# LimitSwitchandMotorBoard.net
KiCad netlist of a schematic drawn in EAGLE
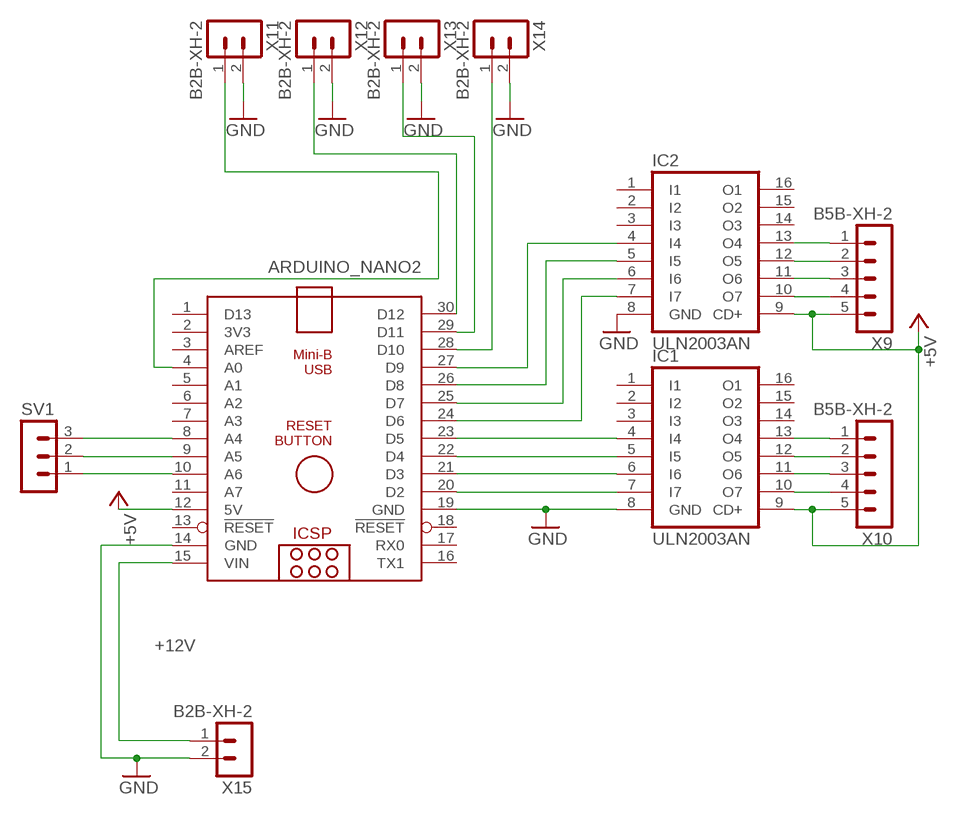
[diagram p0: schematic, sheet 1]

(export (version "E")
  (design (tool "Eeschema 10.0.6"))
  (components
    (comp (ref "ARDUINO_NANO2")
      (value "ARDUINO_NANO")
      (footprint "eagle-import:ARDUINO_NANO")
      (libsource (lib "eagle-import") (part "ARDUINO_NANO"))
    )
    (comp (ref "IC1")
      (value "ULN2003AN")
      (footprint "eagle-import:DIL16")
      (libsource (lib "eagle-import") (part "ULN2003AN"))
    )
    (comp (ref "IC2")
      (value "ULN2003AN")
      (footprint "eagle-import:DIL16")
      (libsource (lib "eagle-import") (part "ULN2003AN"))
    )
    (comp (ref "SV1")
      (value "MA03-1")
      (footprint "eagle-import:MA03-1")
      (libsource (lib "eagle-import") (part "MA03-1"))
    )
    (comp (ref "X9")
      (value "B5B-XH-2")
      (footprint "eagle-import:B5B-XH-A")
      (libsource (lib "eagle-import") (part "B5B-XH-2"))
    )
    (comp (ref "X10")
      (value "B5B-XH-2")
      (footprint "eagle-import:B5B-XH-A")
      (libsource (lib "eagle-import") (part "B5B-XH-2"))
    )
    (comp (ref "X11")
      (value "B2B-XH-2")
      (footprint "eagle-import:B2B-XH-A")
      (libsource (lib "eagle-import") (part "B2B-XH-2"))
    )
    (comp (ref "X12")
      (value "B2B-XH-2")
      (footprint "eagle-import:B2B-XH-A")
      (libsource (lib "eagle-import") (part "B2B-XH-2"))
    )
    (comp (ref "X13")
      (value "B2B-XH-2")
      (footprint "eagle-import:B2B-XH-A")
      (libsource (lib "eagle-import") (part "B2B-XH-2"))
    )
    (comp (ref "X14")
      (value "B2B-XH-2")
      (footprint "eagle-import:B2B-XH-A")
      (libsource (lib "eagle-import") (part "B2B-XH-2"))
    )
    (comp (ref "X15")
      (value "B2B-XH-2")
      (footprint "eagle-import:B2B-XH-A")
      (libsource (lib "eagle-import") (part "B2B-XH-2"))
    )
  )
  (nets
    (net (code "1") (name "+5V") (class "Default")
      (node (ref "ARDUINO_NANO2") (pin "12") (pinfunction "5V_12") (pintype "power_in"))
      (node (ref "IC1") (pin "9") (pinfunction "CD+_9") (pintype "passive"))
      (node (ref "IC2") (pin "9") (pinfunction "CD+_9") (pintype "passive"))
      (node (ref "X10") (pin "5") (pinfunction "5_5") (pintype "passive"))
      (node (ref "X9") (pin "5") (pinfunction "5_5") (pintype "passive"))
    )
    (net (code "2") (name "/+12V") (class "Default")
      (node (ref "ARDUINO_NANO2") (pin "15") (pinfunction "VIN_15") (pintype "power_in"))
      (node (ref "X15") (pin "1") (pinfunction "1_1") (pintype "passive"))
    )
    (net (code "3") (name "GND") (class "Default")
      (node (ref "ARDUINO_NANO2") (pin "14") (pinfunction "GND_14") (pintype "power_in"))
      (node (ref "ARDUINO_NANO2") (pin "19") (pinfunction "GND_19") (pintype "power_in"))
      (node (ref "IC1") (pin "8") (pinfunction "GND_8") (pintype "power_in"))
      (node (ref "IC2") (pin "8") (pinfunction "GND_8") (pintype "power_in"))
      (node (ref "X11") (pin "2") (pinfunction "2_2") (pintype "passive"))
      (node (ref "X12") (pin "2") (pinfunction "2_2") (pintype "passive"))
      (node (ref "X13") (pin "2") (pinfunction "2_2") (pintype "passive"))
      (node (ref "X14") (pin "2") (pinfunction "2_2") (pintype "passive"))
      (node (ref "X15") (pin "2") (pinfunction "2_2") (pintype "passive"))
    )
    (net (code "4") (name "Net-(ARDUINO_NANO2-A0)") (class "Default")
      (node (ref "ARDUINO_NANO2") (pin "4") (pinfunction "A0_4") (pintype "bidirectional"))
      (node (ref "X11") (pin "1") (pinfunction "1_1") (pintype "passive"))
    )
    (net (code "5") (name "Net-(ARDUINO_NANO2-A4)") (class "Default")
      (node (ref "ARDUINO_NANO2") (pin "8") (pinfunction "A4_8") (pintype "bidirectional"))
      (node (ref "SV1") (pin "3") (pinfunction "3_3") (pintype "passive"))
    )
    (net (code "6") (name "Net-(ARDUINO_NANO2-A5)") (class "Default")
      (node (ref "ARDUINO_NANO2") (pin "9") (pinfunction "A5_9") (pintype "bidirectional"))
      (node (ref "SV1") (pin "2") (pinfunction "2_2") (pintype "passive"))
    )
    (net (code "7") (name "Net-(ARDUINO_NANO2-A6)") (class "Default")
      (node (ref "ARDUINO_NANO2") (pin "10") (pinfunction "A6_10") (pintype "bidirectional"))
      (node (ref "SV1") (pin "1") (pinfunction "1_1") (pintype "passive"))
    )
    (net (code "8") (name "Net-(ARDUINO_NANO2-D2)") (class "Default")
      (node (ref "ARDUINO_NANO2") (pin "20") (pinfunction "D2_20") (pintype "bidirectional"))
      (node (ref "IC1") (pin "7") (pinfunction "I7_7") (pintype "input"))
    )
    (net (code "9") (name "Net-(ARDUINO_NANO2-D3)") (class "Default")
      (node (ref "ARDUINO_NANO2") (pin "21") (pinfunction "D3_21") (pintype "bidirectional"))
      (node (ref "IC1") (pin "6") (pinfunction "I6_6") (pintype "input"))
    )
    (net (code "10") (name "Net-(ARDUINO_NANO2-D4)") (class "Default")
      (node (ref "ARDUINO_NANO2") (pin "22") (pinfunction "D4_22") (pintype "bidirectional"))
      (node (ref "IC1") (pin "5") (pinfunction "I5_5") (pintype "input"))
    )
    (net (code "11") (name "Net-(ARDUINO_NANO2-D5)") (class "Default")
      (node (ref "ARDUINO_NANO2") (pin "23") (pinfunction "D5_23") (pintype "bidirectional"))
      (node (ref "IC1") (pin "4") (pinfunction "I4_4") (pintype "input"))
    )
    (net (code "12") (name "Net-(ARDUINO_NANO2-D6)") (class "Default")
      (node (ref "ARDUINO_NANO2") (pin "24") (pinfunction "D6_24") (pintype "bidirectional"))
      (node (ref "IC2") (pin "7") (pinfunction "I7_7") (pintype "input"))
    )
    (net (code "13") (name "Net-(ARDUINO_NANO2-D7)") (class "Default")
      (node (ref "ARDUINO_NANO2") (pin "25") (pinfunction "D7_25") (pintype "bidirectional"))
      (node (ref "IC2") (pin "6") (pinfunction "I6_6") (pintype "input"))
    )
    (net (code "14") (name "Net-(ARDUINO_NANO2-D8)") (class "Default")
      (node (ref "ARDUINO_NANO2") (pin "26") (pinfunction "D8_26") (pintype "bidirectional"))
      (node (ref "IC2") (pin "5") (pinfunction "I5_5") (pintype "input"))
    )
    (net (code "15") (name "Net-(ARDUINO_NANO2-D9)") (class "Default")
      (node (ref "ARDUINO_NANO2") (pin "27") (pinfunction "D9_27") (pintype "bidirectional"))
      (node (ref "IC2") (pin "4") (pinfunction "I4_4") (pintype "input"))
    )
    (net (code "16") (name "Net-(ARDUINO_NANO2-D10)") (class "Default")
      (node (ref "ARDUINO_NANO2") (pin "28") (pinfunction "D10_28") (pintype "bidirectional"))
      (node (ref "X14") (pin "1") (pinfunction "1_1") (pintype "passive"))
    )
    (net (code "17") (name "Net-(ARDUINO_NANO2-D11)") (class "Default")
      (node (ref "ARDUINO_NANO2") (pin "29") (pinfunction "D11_29") (pintype "bidirectional"))
      (node (ref "X13") (pin "1") (pinfunction "1_1") (pintype "passive"))
    )
    (net (code "18") (name "Net-(ARDUINO_NANO2-D12)") (class "Default")
      (node (ref "ARDUINO_NANO2") (pin "30") (pinfunction "D12_30") (pintype "bidirectional"))
      (node (ref "X12") (pin "1") (pinfunction "1_1") (pintype "passive"))
    )
    (net (code "19") (name "Net-(IC1-O4)") (class "Default")
      (node (ref "IC1") (pin "13") (pinfunction "O4_13") (pintype "open_collector"))
      (node (ref "X10") (pin "1") (pinfunction "1_1") (pintype "passive"))
    )
    (net (code "20") (name "Net-(IC1-O5)") (class "Default")
      (node (ref "IC1") (pin "12") (pinfunction "O5_12") (pintype "open_collector"))
      (node (ref "X10") (pin "2") (pinfunction "2_2") (pintype "passive"))
    )
    (net (code "21") (name "Net-(IC1-O6)") (class "Default")
      (node (ref "IC1") (pin "11") (pinfunction "O6_11") (pintype "open_collector"))
      (node (ref "X10") (pin "3") (pinfunction "3_3") (pintype "passive"))
    )
    (net (code "22") (name "Net-(IC1-O7)") (class "Default")
      (node (ref "IC1") (pin "10") (pinfunction "O7_10") (pintype "open_collector"))
      (node (ref "X10") (pin "4") (pinfunction "4_4") (pintype "passive"))
    )
    (net (code "23") (name "Net-(IC2-O4)") (class "Default")
      (node (ref "IC2") (pin "13") (pinfunction "O4_13") (pintype "open_collector"))
      (node (ref "X9") (pin "1") (pinfunction "1_1") (pintype "passive"))
    )
    (net (code "24") (name "Net-(IC2-O5)") (class "Default")
      (node (ref "IC2") (pin "12") (pinfunction "O5_12") (pintype "open_collector"))
      (node (ref "X9") (pin "2") (pinfunction "2_2") (pintype "passive"))
    )
    (net (code "25") (name "Net-(IC2-O6)") (class "Default")
      (node (ref "IC2") (pin "11") (pinfunction "O6_11") (pintype "open_collector"))
      (node (ref "X9") (pin "3") (pinfunction "3_3") (pintype "passive"))
    )
    (net (code "26") (name "Net-(IC2-O7)") (class "Default")
      (node (ref "IC2") (pin "10") (pinfunction "O7_10") (pintype "open_collector"))
      (node (ref "X9") (pin "4") (pinfunction "4_4") (pintype "passive"))
    )
    (net (code "27") (name "unconnected-(ARDUINO_NANO2-3V3-Pad2)") (class "Default")
      (node (ref "ARDUINO_NANO2") (pin "2") (pinfunction "3V3_2") (pintype "output"))
    )
    (net (code "28") (name "unconnected-(ARDUINO_NANO2-A1-Pad5)") (class "Default")
      (node (ref "ARDUINO_NANO2") (pin "5") (pinfunction "A1_5") (pintype "bidirectional"))
    )
    (net (code "29") (name "unconnected-(ARDUINO_NANO2-A2-Pad6)") (class "Default")
      (node (ref "ARDUINO_NANO2") (pin "6") (pinfunction "A2_6") (pintype "bidirectional"))
    )
    (net (code "30") (name "unconnected-(ARDUINO_NANO2-A3-Pad7)") (class "Default")
      (node (ref "ARDUINO_NANO2") (pin "7") (pinfunction "A3_7") (pintype "bidirectional"))
    )
    (net (code "31") (name "unconnected-(ARDUINO_NANO2-A7-Pad11)") (class "Default")
      (node (ref "ARDUINO_NANO2") (pin "11") (pinfunction "A7_11") (pintype "bidirectional"))
    )
    (net (code "32") (name "unconnected-(ARDUINO_NANO2-AREF-Pad3)") (class "Default")
      (node (ref "ARDUINO_NANO2") (pin "3") (pinfunction "AREF_3") (pintype "input"))
    )
    (net (code "33") (name "unconnected-(ARDUINO_NANO2-D13-Pad1)") (class "Default")
      (node (ref "ARDUINO_NANO2") (pin "1") (pinfunction "D13_1") (pintype "bidirectional"))
    )
    (net (code "34") (name "unconnected-(ARDUINO_NANO2-RX0-Pad17)") (class "Default")
      (node (ref "ARDUINO_NANO2") (pin "17") (pinfunction "RX0_17") (pintype "bidirectional"))
    )
    (net (code "35") (name "unconnected-(ARDUINO_NANO2-TX1-Pad16)") (class "Default")
      (node (ref "ARDUINO_NANO2") (pin "16") (pinfunction "TX1_16") (pintype "bidirectional"))
    )
    (net (code "36") (name "unconnected-(ARDUINO_NANO2-~{RESET}-Pad13)") (class "Default")
      (node (ref "ARDUINO_NANO2") (pin "13") (pinfunction "~{RESET}_13") (pintype "input"))
    )
    (net (code "37") (name "unconnected-(ARDUINO_NANO2-~{RESET}-Pad18)") (class "Default")
      (node (ref "ARDUINO_NANO2") (pin "18") (pinfunction "~{RESET}_18") (pintype "input"))
    )
    (net (code "38") (name "unconnected-(IC1-I1-Pad1)") (class "Default")
      (node (ref "IC1") (pin "1") (pinfunction "I1_1") (pintype "input"))
    )
    (net (code "39") (name "unconnected-(IC1-I2-Pad2)") (class "Default")
      (node (ref "IC1") (pin "2") (pinfunction "I2_2") (pintype "input"))
    )
    (net (code "40") (name "unconnected-(IC1-I3-Pad3)") (class "Default")
      (node (ref "IC1") (pin "3") (pinfunction "I3_3") (pintype "input"))
    )
    (net (code "41") (name "unconnected-(IC1-O1-Pad16)") (class "Default")
      (node (ref "IC1") (pin "16") (pinfunction "O1_16") (pintype "open_collector"))
    )
    (net (code "42") (name "unconnected-(IC1-O2-Pad15)") (class "Default")
      (node (ref "IC1") (pin "15") (pinfunction "O2_15") (pintype "open_collector"))
    )
    (net (code "43") (name "unconnected-(IC1-O3-Pad14)") (class "Default")
      (node (ref "IC1") (pin "14") (pinfunction "O3_14") (pintype "open_collector"))
    )
    (net (code "44") (name "unconnected-(IC2-I1-Pad1)") (class "Default")
      (node (ref "IC2") (pin "1") (pinfunction "I1_1") (pintype "input"))
    )
    (net (code "45") (name "unconnected-(IC2-I2-Pad2)") (class "Default")
      (node (ref "IC2") (pin "2") (pinfunction "I2_2") (pintype "input"))
    )
    (net (code "46") (name "unconnected-(IC2-I3-Pad3)") (class "Default")
      (node (ref "IC2") (pin "3") (pinfunction "I3_3") (pintype "input"))
    )
    (net (code "47") (name "unconnected-(IC2-O1-Pad16)") (class "Default")
      (node (ref "IC2") (pin "16") (pinfunction "O1_16") (pintype "open_collector"))
    )
    (net (code "48") (name "unconnected-(IC2-O2-Pad15)") (class "Default")
      (node (ref "IC2") (pin "15") (pinfunction "O2_15") (pintype "open_collector"))
    )
    (net (code "49") (name "unconnected-(IC2-O3-Pad14)") (class "Default")
      (node (ref "IC2") (pin "14") (pinfunction "O3_14") (pintype "open_collector"))
    )
  )
)
